# arduinoJhon.net
KiCad netlist of a schematic drawn in EAGLE
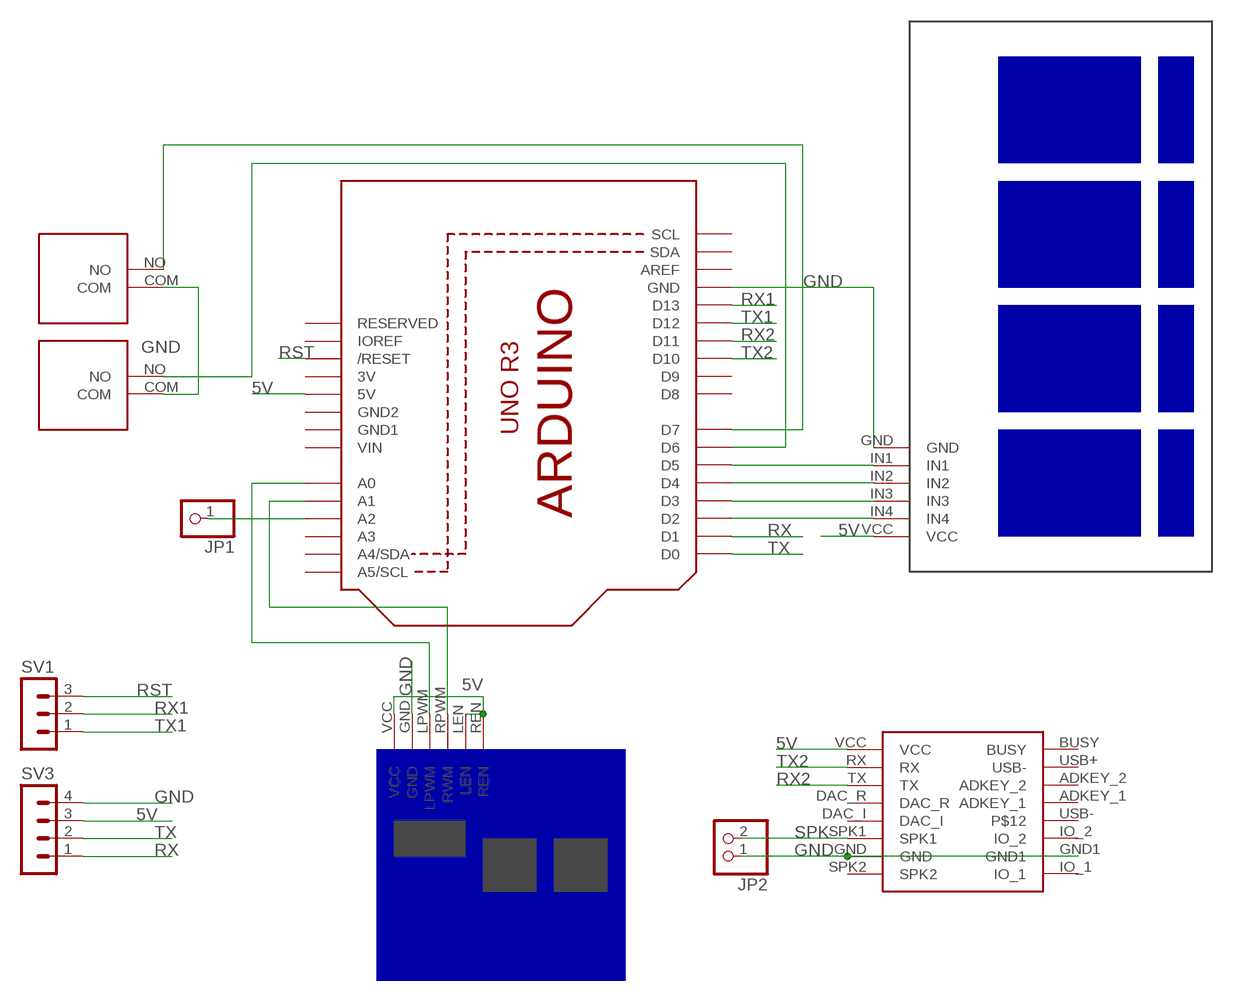
[diagram p0: schematic, sheet 1]

(export (version "E")
  (design (tool "Eeschema 10.0.6"))
  (components
    (comp (ref "JP1")
      (value "PINHD-1X1")
      (footprint "eagle-import:1X01")
      (libsource (lib "eagle-import") (part "PINHD-1X1"))
    )
    (comp (ref "JP2")
      (value "PINHD-1X2")
      (footprint "eagle-import:1X02")
      (libsource (lib "eagle-import") (part "PINHD-1X2"))
    )
    (comp (ref "SV1")
      (value "MA03-1")
      (footprint "eagle-import:MA03-1")
      (libsource (lib "eagle-import") (part "MA03-1"))
    )
    (comp (ref "SV3")
      (value "MA04-1")
      (footprint "eagle-import:MA04-1")
      (libsource (lib "eagle-import") (part "MA04-1"))
    )
    (comp (ref "U$1")
      (value "DFPLAYER_MINI")
      (footprint "eagle-import:DFPLAYER_MINI")
      (libsource (lib "eagle-import") (part "DFPLAYER_MINI"))
    )
    (comp (ref "U$2")
      (value "ARDUINO_UNO")
      (footprint "eagle-import:ARDUINO_UNO")
      (libsource (lib "eagle-import") (part "ARDUINO_UNO"))
    )
    (comp (ref "U$9")
      (value "RELAY_4CHANNEL")
      (footprint "eagle-import:RELAY_4CHANNEL")
      (libsource (lib "eagle-import") (part "RELAY_4CHANNEL"))
    )
    (comp (ref "U$10")
      (value "MOTOR_DRIVER_BTS7960")
      (footprint "eagle-import:MOTOR_DRIVER_BTS7960")
      (libsource (lib "eagle-import") (part "MOTOR_DRIVER_BTS7960"))
    )
    (comp (ref "U$11")
      (value "SWITCHLIMITER")
      (footprint "eagle-import:SWICHLIMITER")
      (libsource (lib "eagle-import") (part "SWITCHLIMITER"))
    )
    (comp (ref "U$12")
      (value "SWITCHLIMITER")
      (footprint "eagle-import:SWICHLIMITER")
      (libsource (lib "eagle-import") (part "SWITCHLIMITER"))
    )
  )
  (nets
    (net (code "1") (name "/3V") (class "Default")
      (node (ref "U$2") (pin "3V") (pinfunction "3V_3V") (pintype "power_in"))
    )
    (net (code "2") (name "/5V") (class "Default")
      (node (ref "SV3") (pin "3") (pinfunction "3_3") (pintype "passive"))
      (node (ref "U$1") (pin "VCC") (pinfunction "VCC_VCC") (pintype "bidirectional"))
      (node (ref "U$10") (pin "LEN") (pinfunction "LEN_LEN") (pintype "bidirectional"))
      (node (ref "U$10") (pin "REN") (pinfunction "REN_REN") (pintype "bidirectional"))
      (node (ref "U$10") (pin "VCC") (pinfunction "VCC_VCC") (pintype "bidirectional"))
      (node (ref "U$2") (pin "5V") (pinfunction "5V_5V") (pintype "power_in"))
      (node (ref "U$9") (pin "VCC") (pinfunction "VCC_VCC") (pintype "bidirectional"))
    )
    (net (code "3") (name "/GND") (class "Default")
      (node (ref "JP2") (pin "1") (pinfunction "1_1") (pintype "passive"))
      (node (ref "SV3") (pin "4") (pinfunction "4_4") (pintype "passive"))
      (node (ref "U$1") (pin "GND") (pinfunction "GND_GND") (pintype "bidirectional"))
      (node (ref "U$1") (pin "GND1") (pinfunction "GND1_GND1") (pintype "bidirectional"))
      (node (ref "U$10") (pin "GND") (pinfunction "GND_GND") (pintype "bidirectional"))
      (node (ref "U$11") (pin "COM") (pinfunction "COM_COM") (pintype "bidirectional"))
      (node (ref "U$12") (pin "COM") (pinfunction "COM_COM") (pintype "bidirectional"))
      (node (ref "U$2") (pin "GND") (pinfunction "GND_GND") (pintype "power_in"))
      (node (ref "U$9") (pin "GND") (pinfunction "GND_GND") (pintype "bidirectional"))
    )
    (net (code "4") (name "/GND1") (class "Default")
      (node (ref "U$2") (pin "GND1") (pinfunction "GND1_GND1") (pintype "power_in"))
    )
    (net (code "5") (name "/GND2") (class "Default")
      (node (ref "U$2") (pin "GND2") (pinfunction "GND2_GND2") (pintype "power_in"))
    )
    (net (code "6") (name "/RST") (class "Default")
      (node (ref "SV1") (pin "3") (pinfunction "3_3") (pintype "passive"))
      (node (ref "U$2") (pin "RESET") (pinfunction "/RESET_RESET") (pintype "bidirectional"))
    )
    (net (code "7") (name "/RX") (class "Default")
      (node (ref "SV3") (pin "1") (pinfunction "1_1") (pintype "passive"))
      (node (ref "U$2") (pin "D1") (pinfunction "D1_D1") (pintype "bidirectional"))
    )
    (net (code "8") (name "/RX1") (class "Default")
      (node (ref "SV1") (pin "2") (pinfunction "2_2") (pintype "passive"))
      (node (ref "U$2") (pin "D13") (pinfunction "D13_D13") (pintype "bidirectional"))
    )
    (net (code "9") (name "/RX2") (class "Default")
      (node (ref "U$1") (pin "TX") (pinfunction "TX_TX") (pintype "bidirectional"))
      (node (ref "U$2") (pin "D11") (pinfunction "D11_D11") (pintype "bidirectional"))
    )
    (net (code "10") (name "/SPK") (class "Default")
      (node (ref "JP2") (pin "2") (pinfunction "2_2") (pintype "passive"))
      (node (ref "U$1") (pin "SPK1") (pinfunction "SPK1_SPK1") (pintype "bidirectional"))
    )
    (net (code "11") (name "/TX") (class "Default")
      (node (ref "SV3") (pin "2") (pinfunction "2_2") (pintype "passive"))
      (node (ref "U$2") (pin "D0") (pinfunction "D0_D0") (pintype "bidirectional"))
    )
    (net (code "12") (name "/TX1") (class "Default")
      (node (ref "SV1") (pin "1") (pinfunction "1_1") (pintype "passive"))
      (node (ref "U$2") (pin "D12") (pinfunction "D12_D12") (pintype "bidirectional"))
    )
    (net (code "13") (name "/TX2") (class "Default")
      (node (ref "U$1") (pin "RX") (pinfunction "RX_RX") (pintype "bidirectional"))
      (node (ref "U$2") (pin "D10") (pinfunction "D10_D10") (pintype "bidirectional"))
    )
    (net (code "14") (name "/VIN") (class "Default")
      (node (ref "U$2") (pin "VIN") (pinfunction "VIN_VIN") (pintype "power_in"))
    )
    (net (code "15") (name "Net-(JP1-Pad1)") (class "Default")
      (node (ref "JP1") (pin "1") (pinfunction "1_1") (pintype "passive"))
      (node (ref "U$2") (pin "A2") (pinfunction "A2_A2") (pintype "bidirectional"))
    )
    (net (code "16") (name "Net-(U$2-PadD2)") (class "Default")
      (node (ref "U$2") (pin "D2") (pinfunction "D2_D2") (pintype "bidirectional"))
      (node (ref "U$9") (pin "IN4") (pinfunction "IN4_IN4") (pintype "bidirectional"))
    )
    (net (code "17") (name "Net-(U$2-PadD3)") (class "Default")
      (node (ref "U$2") (pin "D3") (pinfunction "D3_D3") (pintype "bidirectional"))
      (node (ref "U$9") (pin "IN3") (pinfunction "IN3_IN3") (pintype "bidirectional"))
    )
    (net (code "18") (name "Net-(U$2-PadD4)") (class "Default")
      (node (ref "U$2") (pin "D4") (pinfunction "D4_D4") (pintype "bidirectional"))
      (node (ref "U$9") (pin "IN2") (pinfunction "IN2_IN2") (pintype "bidirectional"))
    )
    (net (code "19") (name "Net-(U$2-PadD5)") (class "Default")
      (node (ref "U$2") (pin "D5") (pinfunction "D5_D5") (pintype "bidirectional"))
      (node (ref "U$9") (pin "IN1") (pinfunction "IN1_IN1") (pintype "bidirectional"))
    )
    (net (code "20") (name "Net-(U$10-PadLPWM)") (class "Default")
      (node (ref "U$10") (pin "LPWM") (pinfunction "LPWM_LPWM") (pintype "bidirectional"))
      (node (ref "U$2") (pin "A0") (pinfunction "A0_A0") (pintype "bidirectional"))
    )
    (net (code "21") (name "Net-(U$10-RWM)") (class "Default")
      (node (ref "U$10") (pin "RPWM") (pinfunction "RWM_RPWM") (pintype "bidirectional"))
      (node (ref "U$2") (pin "A1") (pinfunction "A1_A1") (pintype "bidirectional"))
    )
    (net (code "22") (name "Net-(U$11-PadNO)") (class "Default")
      (node (ref "U$11") (pin "NO") (pinfunction "NO_NO") (pintype "bidirectional"))
      (node (ref "U$2") (pin "D7") (pinfunction "D7_D7") (pintype "bidirectional"))
    )
    (net (code "23") (name "Net-(U$12-PadNO)") (class "Default")
      (node (ref "U$12") (pin "NO") (pinfunction "NO_NO") (pintype "bidirectional"))
      (node (ref "U$2") (pin "D6") (pinfunction "D6_D6") (pintype "bidirectional"))
    )
    (net (code "24") (name "unconnected-(U$1-P$12-PadUSB-)") (class "Default")
      (node (ref "U$1") (pin "USB-") (pinfunction "P$12_USB-") (pintype "bidirectional"))
    )
    (net (code "25") (name "unconnected-(U$1-PadADKEY_1)") (class "Default")
      (node (ref "U$1") (pin "ADKEY_1") (pinfunction "ADKEY_1_ADKEY_1") (pintype "bidirectional"))
    )
    (net (code "26") (name "unconnected-(U$1-PadADKEY_2)") (class "Default")
      (node (ref "U$1") (pin "ADKEY_2") (pinfunction "ADKEY_2_ADKEY_2") (pintype "bidirectional"))
    )
    (net (code "27") (name "unconnected-(U$1-PadBUSY)") (class "Default")
      (node (ref "U$1") (pin "BUSY") (pinfunction "BUSY_BUSY") (pintype "bidirectional"))
    )
    (net (code "28") (name "unconnected-(U$1-PadDAC_I)") (class "Default")
      (node (ref "U$1") (pin "DAC_I") (pinfunction "DAC_I_DAC_I") (pintype "bidirectional"))
    )
    (net (code "29") (name "unconnected-(U$1-PadDAC_R)") (class "Default")
      (node (ref "U$1") (pin "DAC_R") (pinfunction "DAC_R_DAC_R") (pintype "bidirectional"))
    )
    (net (code "30") (name "unconnected-(U$1-PadIO_1)") (class "Default")
      (node (ref "U$1") (pin "IO_1") (pinfunction "IO_1_IO_1") (pintype "bidirectional"))
    )
    (net (code "31") (name "unconnected-(U$1-PadIO_2)") (class "Default")
      (node (ref "U$1") (pin "IO_2") (pinfunction "IO_2_IO_2") (pintype "bidirectional"))
    )
    (net (code "32") (name "unconnected-(U$1-PadSPK2)") (class "Default")
      (node (ref "U$1") (pin "SPK2") (pinfunction "SPK2_SPK2") (pintype "bidirectional"))
    )
    (net (code "33") (name "unconnected-(U$1-USB--PadUSB+)") (class "Default")
      (node (ref "U$1") (pin "USB+") (pinfunction "USB-_USB+") (pintype "bidirectional"))
    )
    (net (code "34") (name "unconnected-(U$2-A4{slash}SDA-PadA4)") (class "Default")
      (node (ref "U$2") (pin "A4") (pinfunction "A4/SDA_A4") (pintype "bidirectional"))
    )
    (net (code "35") (name "unconnected-(U$2-A5{slash}SCL-PadA5)") (class "Default")
      (node (ref "U$2") (pin "A5") (pinfunction "A5/SCL_A5") (pintype "bidirectional"))
    )
    (net (code "36") (name "unconnected-(U$2-PadA3)") (class "Default")
      (node (ref "U$2") (pin "A3") (pinfunction "A3_A3") (pintype "bidirectional"))
    )
    (net (code "37") (name "unconnected-(U$2-PadAREF)") (class "Default")
      (node (ref "U$2") (pin "AREF") (pinfunction "AREF_AREF") (pintype "bidirectional"))
    )
    (net (code "38") (name "unconnected-(U$2-PadD8)") (class "Default")
      (node (ref "U$2") (pin "D8") (pinfunction "D8_D8") (pintype "bidirectional"))
    )
    (net (code "39") (name "unconnected-(U$2-PadD9)") (class "Default")
      (node (ref "U$2") (pin "D9") (pinfunction "D9_D9") (pintype "bidirectional"))
    )
    (net (code "40") (name "unconnected-(U$2-PadIOREF)") (class "Default")
      (node (ref "U$2") (pin "IOREF") (pinfunction "IOREF_IOREF") (pintype "output"))
    )
    (net (code "41") (name "unconnected-(U$2-PadRESERVED)") (class "Default")
      (node (ref "U$2") (pin "RESERVED") (pinfunction "RESERVED_RESERVED") (pintype "no_connect"))
    )
    (net (code "42") (name "unconnected-(U$2-PadSCL)") (class "Default")
      (node (ref "U$2") (pin "SCL") (pinfunction "SCL_SCL") (pintype "bidirectional"))
    )
    (net (code "43") (name "unconnected-(U$2-PadSDA)") (class "Default")
      (node (ref "U$2") (pin "SDA") (pinfunction "SDA_SDA") (pintype "bidirectional"))
    )
  )
)
